# Capsense16_25092018.net
KiCad netlist of a schematic drawn in EAGLE
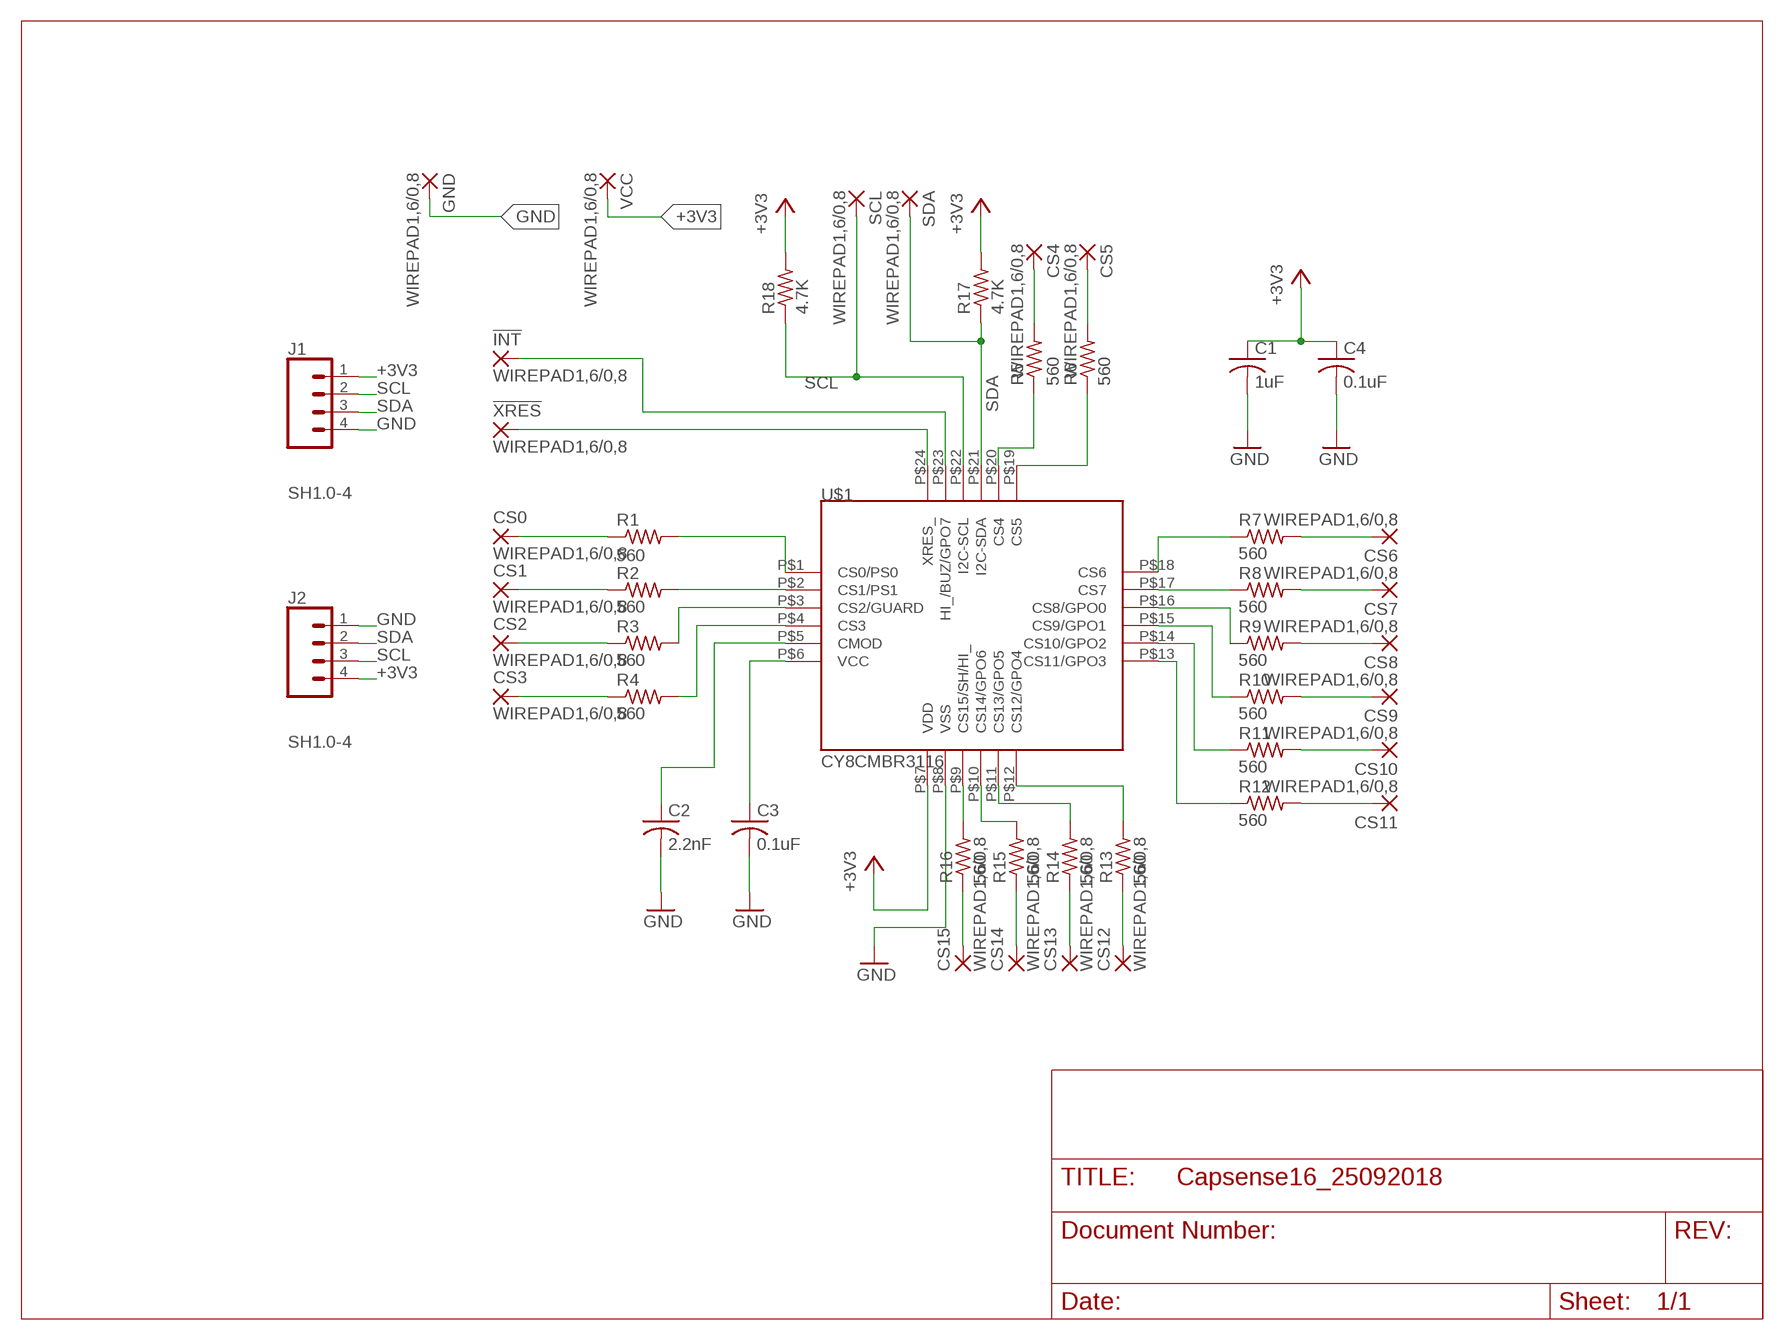
[diagram p0: schematic, sheet 1]

(export (version "E")
  (design (tool "Eeschema 10.0.6"))
  (components
    (comp (ref "!INT!")
      (value "WIREPAD1,6/0,8")
      (footprint "eagle-import:1,6_0,8")
      (libsource (lib "eagle-import") (part "WIREPAD1,6/0,8"))
    )
    (comp (ref "!XRES!")
      (value "WIREPAD1,6/0,8")
      (footprint "eagle-import:1,6_0,8")
      (libsource (lib "eagle-import") (part "WIREPAD1,6/0,8"))
    )
    (comp (ref "C1")
      (value "1uF")
      (footprint "eagle-import:C0603")
      (libsource (lib "eagle-import") (part "C-USC0603"))
    )
    (comp (ref "C2")
      (value "2.2nF")
      (footprint "eagle-import:C0603")
      (libsource (lib "eagle-import") (part "C-USC0603"))
    )
    (comp (ref "C3")
      (value "0.1uF")
      (footprint "eagle-import:C0603")
      (libsource (lib "eagle-import") (part "C-USC0603"))
    )
    (comp (ref "C4")
      (value "0.1uF")
      (footprint "eagle-import:C0603")
      (libsource (lib "eagle-import") (part "C-USC0603"))
    )
    (comp (ref "CS0")
      (value "WIREPAD1,6/0,8")
      (footprint "eagle-import:1,6_0,8")
      (libsource (lib "eagle-import") (part "WIREPAD1,6/0,8"))
    )
    (comp (ref "CS1")
      (value "WIREPAD1,6/0,8")
      (footprint "eagle-import:1,6_0,8")
      (libsource (lib "eagle-import") (part "WIREPAD1,6/0,8"))
    )
    (comp (ref "CS2")
      (value "WIREPAD1,6/0,8")
      (footprint "eagle-import:1,6_0,8")
      (libsource (lib "eagle-import") (part "WIREPAD1,6/0,8"))
    )
    (comp (ref "CS3")
      (value "WIREPAD1,6/0,8")
      (footprint "eagle-import:1,6_0,8")
      (libsource (lib "eagle-import") (part "WIREPAD1,6/0,8"))
    )
    (comp (ref "CS4")
      (value "WIREPAD1,6/0,8")
      (footprint "eagle-import:1,6_0,8")
      (libsource (lib "eagle-import") (part "WIREPAD1,6/0,8"))
    )
    (comp (ref "CS5")
      (value "WIREPAD1,6/0,8")
      (footprint "eagle-import:1,6_0,8")
      (libsource (lib "eagle-import") (part "WIREPAD1,6/0,8"))
    )
    (comp (ref "CS6")
      (value "WIREPAD1,6/0,8")
      (footprint "eagle-import:1,6_0,8")
      (libsource (lib "eagle-import") (part "WIREPAD1,6/0,8"))
    )
    (comp (ref "CS7")
      (value "WIREPAD1,6/0,8")
      (footprint "eagle-import:1,6_0,8")
      (libsource (lib "eagle-import") (part "WIREPAD1,6/0,8"))
    )
    (comp (ref "CS8")
      (value "WIREPAD1,6/0,8")
      (footprint "eagle-import:1,6_0,8")
      (libsource (lib "eagle-import") (part "WIREPAD1,6/0,8"))
    )
    (comp (ref "CS9")
      (value "WIREPAD1,6/0,8")
      (footprint "eagle-import:1,6_0,8")
      (libsource (lib "eagle-import") (part "WIREPAD1,6/0,8"))
    )
    (comp (ref "CS10")
      (value "WIREPAD1,6/0,8")
      (footprint "eagle-import:1,6_0,8")
      (libsource (lib "eagle-import") (part "WIREPAD1,6/0,8"))
    )
    (comp (ref "CS11")
      (value "WIREPAD1,6/0,8")
      (footprint "eagle-import:1,6_0,8")
      (libsource (lib "eagle-import") (part "WIREPAD1,6/0,8"))
    )
    (comp (ref "CS12")
      (value "WIREPAD1,6/0,8")
      (footprint "eagle-import:1,6_0,8")
      (libsource (lib "eagle-import") (part "WIREPAD1,6/0,8"))
    )
    (comp (ref "CS13")
      (value "WIREPAD1,6/0,8")
      (footprint "eagle-import:1,6_0,8")
      (libsource (lib "eagle-import") (part "WIREPAD1,6/0,8"))
    )
    (comp (ref "CS14")
      (value "WIREPAD1,6/0,8")
      (footprint "eagle-import:1,6_0,8")
      (libsource (lib "eagle-import") (part "WIREPAD1,6/0,8"))
    )
    (comp (ref "CS15")
      (value "WIREPAD1,6/0,8")
      (footprint "eagle-import:1,6_0,8")
      (libsource (lib "eagle-import") (part "WIREPAD1,6/0,8"))
    )
    (comp (ref "GND")
      (value "WIREPAD1,6/0,8")
      (footprint "eagle-import:1,6_0,8")
      (libsource (lib "eagle-import") (part "WIREPAD1,6/0,8"))
    )
    (comp (ref "J1")
      (value "SH1.0-4")
      (footprint "eagle-import:JST-4-SMD-HORI-1.0MM")
      (libsource (lib "eagle-import") (part "JST_4_PIN_HORIZONTAL"))
    )
    (comp (ref "J2")
      (value "SH1.0-4")
      (footprint "eagle-import:JST-4-SMD-HORI-1.0MM")
      (libsource (lib "eagle-import") (part "JST_4_PIN_HORIZONTAL"))
    )
    (comp (ref "R1")
      (value "560")
      (footprint "eagle-import:R0603")
      (libsource (lib "eagle-import") (part "R-US_R0603"))
    )
    (comp (ref "R2")
      (value "560")
      (footprint "eagle-import:R0603")
      (libsource (lib "eagle-import") (part "R-US_R0603"))
    )
    (comp (ref "R3")
      (value "560")
      (footprint "eagle-import:R0603")
      (libsource (lib "eagle-import") (part "R-US_R0603"))
    )
    (comp (ref "R4")
      (value "560")
      (footprint "eagle-import:R0603")
      (libsource (lib "eagle-import") (part "R-US_R0603"))
    )
    (comp (ref "R5")
      (value "560")
      (footprint "eagle-import:R0603")
      (libsource (lib "eagle-import") (part "R-US_R0603"))
    )
    (comp (ref "R6")
      (value "560")
      (footprint "eagle-import:R0603")
      (libsource (lib "eagle-import") (part "R-US_R0603"))
    )
    (comp (ref "R7")
      (value "560")
      (footprint "eagle-import:R0603")
      (libsource (lib "eagle-import") (part "R-US_R0603"))
    )
    (comp (ref "R8")
      (value "560")
      (footprint "eagle-import:R0603")
      (libsource (lib "eagle-import") (part "R-US_R0603"))
    )
    (comp (ref "R9")
      (value "560")
      (footprint "eagle-import:R0603")
      (libsource (lib "eagle-import") (part "R-US_R0603"))
    )
    (comp (ref "R10")
      (value "560")
      (footprint "eagle-import:R0603")
      (libsource (lib "eagle-import") (part "R-US_R0603"))
    )
    (comp (ref "R11")
      (value "560")
      (footprint "eagle-import:R0603")
      (libsource (lib "eagle-import") (part "R-US_R0603"))
    )
    (comp (ref "R12")
      (value "560")
      (footprint "eagle-import:R0603")
      (libsource (lib "eagle-import") (part "R-US_R0603"))
    )
    (comp (ref "R13")
      (value "560")
      (footprint "eagle-import:R0603")
      (libsource (lib "eagle-import") (part "R-US_R0603"))
    )
    (comp (ref "R14")
      (value "560")
      (footprint "eagle-import:R0603")
      (libsource (lib "eagle-import") (part "R-US_R0603"))
    )
    (comp (ref "R15")
      (value "560")
      (footprint "eagle-import:R0603")
      (libsource (lib "eagle-import") (part "R-US_R0603"))
    )
    (comp (ref "R16")
      (value "560")
      (footprint "eagle-import:R0603")
      (libsource (lib "eagle-import") (part "R-US_R0603"))
    )
    (comp (ref "R17")
      (value "4.7K")
      (footprint "eagle-import:R0603")
      (libsource (lib "eagle-import") (part "R-US_R0603"))
    )
    (comp (ref "R18")
      (value "4.7K")
      (footprint "eagle-import:R0603")
      (libsource (lib "eagle-import") (part "R-US_R0603"))
    )
    (comp (ref "SCL")
      (value "WIREPAD1,6/0,8")
      (footprint "eagle-import:1,6_0,8")
      (libsource (lib "eagle-import") (part "WIREPAD1,6/0,8"))
    )
    (comp (ref "SDA")
      (value "WIREPAD1,6/0,8")
      (footprint "eagle-import:1,6_0,8")
      (libsource (lib "eagle-import") (part "WIREPAD1,6/0,8"))
    )
    (comp (ref "U$1")
      (value "CY8CMBR3116")
      (footprint "eagle-import:CY8CMBR3116")
      (libsource (lib "eagle-import") (part "CY8CMBR3116"))
    )
    (comp (ref "VCC")
      (value "WIREPAD1,6/0,8")
      (footprint "eagle-import:1,6_0,8")
      (libsource (lib "eagle-import") (part "WIREPAD1,6/0,8"))
    )
  )
  (nets
    (net (code "1") (name "+3V3") (class "Default")
      (node (ref "C1") (pin "1") (pinfunction "1_1") (pintype "passive"))
      (node (ref "C4") (pin "1") (pinfunction "1_1") (pintype "passive"))
      (node (ref "J1") (pin "1") (pinfunction "1_1") (pintype "passive"))
      (node (ref "J2") (pin "4") (pinfunction "4_4") (pintype "passive"))
      (node (ref "R17") (pin "2") (pinfunction "2_2") (pintype "passive"))
      (node (ref "R18") (pin "2") (pinfunction "2_2") (pintype "passive"))
      (node (ref "U$1") (pin "P$7") (pinfunction "VDD_P$7") (pintype "bidirectional"))
      (node (ref "VCC") (pin "1") (pinfunction "P_1") (pintype "passive"))
    )
    (net (code "2") (name "/SCL") (class "Default")
      (node (ref "J1") (pin "2") (pinfunction "2_2") (pintype "passive"))
      (node (ref "J2") (pin "3") (pinfunction "3_3") (pintype "passive"))
      (node (ref "R18") (pin "1") (pinfunction "1_1") (pintype "passive"))
      (node (ref "SCL") (pin "1") (pinfunction "P_1") (pintype "passive"))
      (node (ref "U$1") (pin "P$22") (pinfunction "I2C-SCL_P$22") (pintype "bidirectional"))
    )
    (net (code "3") (name "/SDA") (class "Default")
      (node (ref "J1") (pin "3") (pinfunction "3_3") (pintype "passive"))
      (node (ref "J2") (pin "2") (pinfunction "2_2") (pintype "passive"))
      (node (ref "R17") (pin "1") (pinfunction "1_1") (pintype "passive"))
      (node (ref "SDA") (pin "1") (pinfunction "P_1") (pintype "passive"))
      (node (ref "U$1") (pin "P$21") (pinfunction "I2C-SDA_P$21") (pintype "bidirectional"))
    )
    (net (code "4") (name "GND") (class "Default")
      (node (ref "C1") (pin "2") (pinfunction "2_2") (pintype "passive"))
      (node (ref "C2") (pin "2") (pinfunction "2_2") (pintype "passive"))
      (node (ref "C3") (pin "2") (pinfunction "2_2") (pintype "passive"))
      (node (ref "C4") (pin "2") (pinfunction "2_2") (pintype "passive"))
      (node (ref "GND") (pin "1") (pinfunction "P_1") (pintype "passive"))
      (node (ref "J1") (pin "4") (pinfunction "4_4") (pintype "passive"))
      (node (ref "J2") (pin "1") (pinfunction "1_1") (pintype "passive"))
      (node (ref "U$1") (pin "P$8") (pinfunction "VSS_P$8") (pintype "bidirectional"))
    )
    (net (code "5") (name "Net-(!INT!-P)") (class "Default")
      (node (ref "!INT!") (pin "1") (pinfunction "P_1") (pintype "passive"))
      (node (ref "U$1") (pin "P$23") (pinfunction "HI_/BUZ/GPO7_P$23") (pintype "bidirectional"))
    )
    (net (code "6") (name "Net-(!XRES!-P)") (class "Default")
      (node (ref "!XRES!") (pin "1") (pinfunction "P_1") (pintype "passive"))
      (node (ref "U$1") (pin "P$24") (pinfunction "XRES__P$24") (pintype "bidirectional"))
    )
    (net (code "7") (name "Net-(CS0-P)") (class "Default")
      (node (ref "CS0") (pin "1") (pinfunction "P_1") (pintype "passive"))
      (node (ref "R1") (pin "1") (pinfunction "1_1") (pintype "passive"))
    )
    (net (code "8") (name "Net-(CS1-P)") (class "Default")
      (node (ref "CS1") (pin "1") (pinfunction "P_1") (pintype "passive"))
      (node (ref "R2") (pin "1") (pinfunction "1_1") (pintype "passive"))
    )
    (net (code "9") (name "Net-(CS2-P)") (class "Default")
      (node (ref "CS2") (pin "1") (pinfunction "P_1") (pintype "passive"))
      (node (ref "R3") (pin "1") (pinfunction "1_1") (pintype "passive"))
    )
    (net (code "10") (name "Net-(CS3-P)") (class "Default")
      (node (ref "CS3") (pin "1") (pinfunction "P_1") (pintype "passive"))
      (node (ref "R4") (pin "1") (pinfunction "1_1") (pintype "passive"))
    )
    (net (code "11") (name "Net-(CS4-P)") (class "Default")
      (node (ref "CS4") (pin "1") (pinfunction "P_1") (pintype "passive"))
      (node (ref "R5") (pin "2") (pinfunction "2_2") (pintype "passive"))
    )
    (net (code "12") (name "Net-(CS5-P)") (class "Default")
      (node (ref "CS5") (pin "1") (pinfunction "P_1") (pintype "passive"))
      (node (ref "R6") (pin "2") (pinfunction "2_2") (pintype "passive"))
    )
    (net (code "13") (name "Net-(CS6-P)") (class "Default")
      (node (ref "CS6") (pin "1") (pinfunction "P_1") (pintype "passive"))
      (node (ref "R7") (pin "2") (pinfunction "2_2") (pintype "passive"))
    )
    (net (code "14") (name "Net-(CS7-P)") (class "Default")
      (node (ref "CS7") (pin "1") (pinfunction "P_1") (pintype "passive"))
      (node (ref "R8") (pin "2") (pinfunction "2_2") (pintype "passive"))
    )
    (net (code "15") (name "Net-(CS8-P)") (class "Default")
      (node (ref "CS8") (pin "1") (pinfunction "P_1") (pintype "passive"))
      (node (ref "R9") (pin "2") (pinfunction "2_2") (pintype "passive"))
    )
    (net (code "16") (name "Net-(CS9-P)") (class "Default")
      (node (ref "CS9") (pin "1") (pinfunction "P_1") (pintype "passive"))
      (node (ref "R10") (pin "2") (pinfunction "2_2") (pintype "passive"))
    )
    (net (code "17") (name "Net-(CS10-P)") (class "Default")
      (node (ref "CS10") (pin "1") (pinfunction "P_1") (pintype "passive"))
      (node (ref "R11") (pin "2") (pinfunction "2_2") (pintype "passive"))
    )
    (net (code "18") (name "Net-(CS11-P)") (class "Default")
      (node (ref "CS11") (pin "1") (pinfunction "P_1") (pintype "passive"))
      (node (ref "R12") (pin "2") (pinfunction "2_2") (pintype "passive"))
    )
    (net (code "19") (name "Net-(CS12-P)") (class "Default")
      (node (ref "CS12") (pin "1") (pinfunction "P_1") (pintype "passive"))
      (node (ref "R13") (pin "1") (pinfunction "1_1") (pintype "passive"))
    )
    (net (code "20") (name "Net-(CS13-P)") (class "Default")
      (node (ref "CS13") (pin "1") (pinfunction "P_1") (pintype "passive"))
      (node (ref "R14") (pin "1") (pinfunction "1_1") (pintype "passive"))
    )
    (net (code "21") (name "Net-(CS14-P)") (class "Default")
      (node (ref "CS14") (pin "1") (pinfunction "P_1") (pintype "passive"))
      (node (ref "R15") (pin "1") (pinfunction "1_1") (pintype "passive"))
    )
    (net (code "22") (name "Net-(CS15-P)") (class "Default")
      (node (ref "CS15") (pin "1") (pinfunction "P_1") (pintype "passive"))
      (node (ref "R16") (pin "1") (pinfunction "1_1") (pintype "passive"))
    )
    (net (code "23") (name "Net-(U$1-CMOD)") (class "Default")
      (node (ref "C2") (pin "1") (pinfunction "1_1") (pintype "passive"))
      (node (ref "U$1") (pin "P$5") (pinfunction "CMOD_P$5") (pintype "bidirectional"))
    )
    (net (code "24") (name "Net-(U$1-CS0{slash}PS0)") (class "Default")
      (node (ref "R1") (pin "2") (pinfunction "2_2") (pintype "passive"))
      (node (ref "U$1") (pin "P$1") (pinfunction "CS0/PS0_P$1") (pintype "bidirectional"))
    )
    (net (code "25") (name "Net-(U$1-CS1{slash}PS1)") (class "Default")
      (node (ref "R2") (pin "2") (pinfunction "2_2") (pintype "passive"))
      (node (ref "U$1") (pin "P$2") (pinfunction "CS1/PS1_P$2") (pintype "bidirectional"))
    )
    (net (code "26") (name "Net-(U$1-CS2{slash}GUARD)") (class "Default")
      (node (ref "R3") (pin "2") (pinfunction "2_2") (pintype "passive"))
      (node (ref "U$1") (pin "P$3") (pinfunction "CS2/GUARD_P$3") (pintype "bidirectional"))
    )
    (net (code "27") (name "Net-(U$1-CS3)") (class "Default")
      (node (ref "R4") (pin "2") (pinfunction "2_2") (pintype "passive"))
      (node (ref "U$1") (pin "P$4") (pinfunction "CS3_P$4") (pintype "bidirectional"))
    )
    (net (code "28") (name "Net-(U$1-CS4)") (class "Default")
      (node (ref "R5") (pin "1") (pinfunction "1_1") (pintype "passive"))
      (node (ref "U$1") (pin "P$20") (pinfunction "CS4_P$20") (pintype "bidirectional"))
    )
    (net (code "29") (name "Net-(U$1-CS5)") (class "Default")
      (node (ref "R6") (pin "1") (pinfunction "1_1") (pintype "passive"))
      (node (ref "U$1") (pin "P$19") (pinfunction "CS5_P$19") (pintype "bidirectional"))
    )
    (net (code "30") (name "Net-(U$1-CS6)") (class "Default")
      (node (ref "R7") (pin "1") (pinfunction "1_1") (pintype "passive"))
      (node (ref "U$1") (pin "P$18") (pinfunction "CS6_P$18") (pintype "bidirectional"))
    )
    (net (code "31") (name "Net-(U$1-CS7)") (class "Default")
      (node (ref "R8") (pin "1") (pinfunction "1_1") (pintype "passive"))
      (node (ref "U$1") (pin "P$17") (pinfunction "CS7_P$17") (pintype "bidirectional"))
    )
    (net (code "32") (name "Net-(U$1-CS8{slash}GPO0)") (class "Default")
      (node (ref "R9") (pin "1") (pinfunction "1_1") (pintype "passive"))
      (node (ref "U$1") (pin "P$16") (pinfunction "CS8/GPO0_P$16") (pintype "bidirectional"))
    )
    (net (code "33") (name "Net-(U$1-CS9{slash}GPO1)") (class "Default")
      (node (ref "R10") (pin "1") (pinfunction "1_1") (pintype "passive"))
      (node (ref "U$1") (pin "P$15") (pinfunction "CS9/GPO1_P$15") (pintype "bidirectional"))
    )
    (net (code "34") (name "Net-(U$1-CS10{slash}GPO2)") (class "Default")
      (node (ref "R11") (pin "1") (pinfunction "1_1") (pintype "passive"))
      (node (ref "U$1") (pin "P$14") (pinfunction "CS10/GPO2_P$14") (pintype "bidirectional"))
    )
    (net (code "35") (name "Net-(U$1-CS11{slash}GPO3)") (class "Default")
      (node (ref "R12") (pin "1") (pinfunction "1_1") (pintype "passive"))
      (node (ref "U$1") (pin "P$13") (pinfunction "CS11/GPO3_P$13") (pintype "bidirectional"))
    )
    (net (code "36") (name "Net-(U$1-CS12{slash}GPO4)") (class "Default")
      (node (ref "R13") (pin "2") (pinfunction "2_2") (pintype "passive"))
      (node (ref "U$1") (pin "P$12") (pinfunction "CS12/GPO4_P$12") (pintype "bidirectional"))
    )
    (net (code "37") (name "Net-(U$1-CS13{slash}GPO5)") (class "Default")
      (node (ref "R14") (pin "2") (pinfunction "2_2") (pintype "passive"))
      (node (ref "U$1") (pin "P$11") (pinfunction "CS13/GPO5_P$11") (pintype "bidirectional"))
    )
    (net (code "38") (name "Net-(U$1-CS14{slash}GPO6)") (class "Default")
      (node (ref "R15") (pin "2") (pinfunction "2_2") (pintype "passive"))
      (node (ref "U$1") (pin "P$10") (pinfunction "CS14/GPO6_P$10") (pintype "bidirectional"))
    )
    (net (code "39") (name "Net-(U$1-CS15{slash}SH{slash}HI_)") (class "Default")
      (node (ref "R16") (pin "2") (pinfunction "2_2") (pintype "passive"))
      (node (ref "U$1") (pin "P$9") (pinfunction "CS15/SH/HI__P$9") (pintype "bidirectional"))
    )
    (net (code "40") (name "Net-(U$1-VCC)") (class "Default")
      (node (ref "C3") (pin "1") (pinfunction "1_1") (pintype "passive"))
      (node (ref "U$1") (pin "P$6") (pinfunction "VCC_P$6") (pintype "bidirectional"))
    )
  )
)
